# lt3477-buck-boost-flashlight-driver-17mm.net
KiCad netlist of a schematic drawn in EAGLE
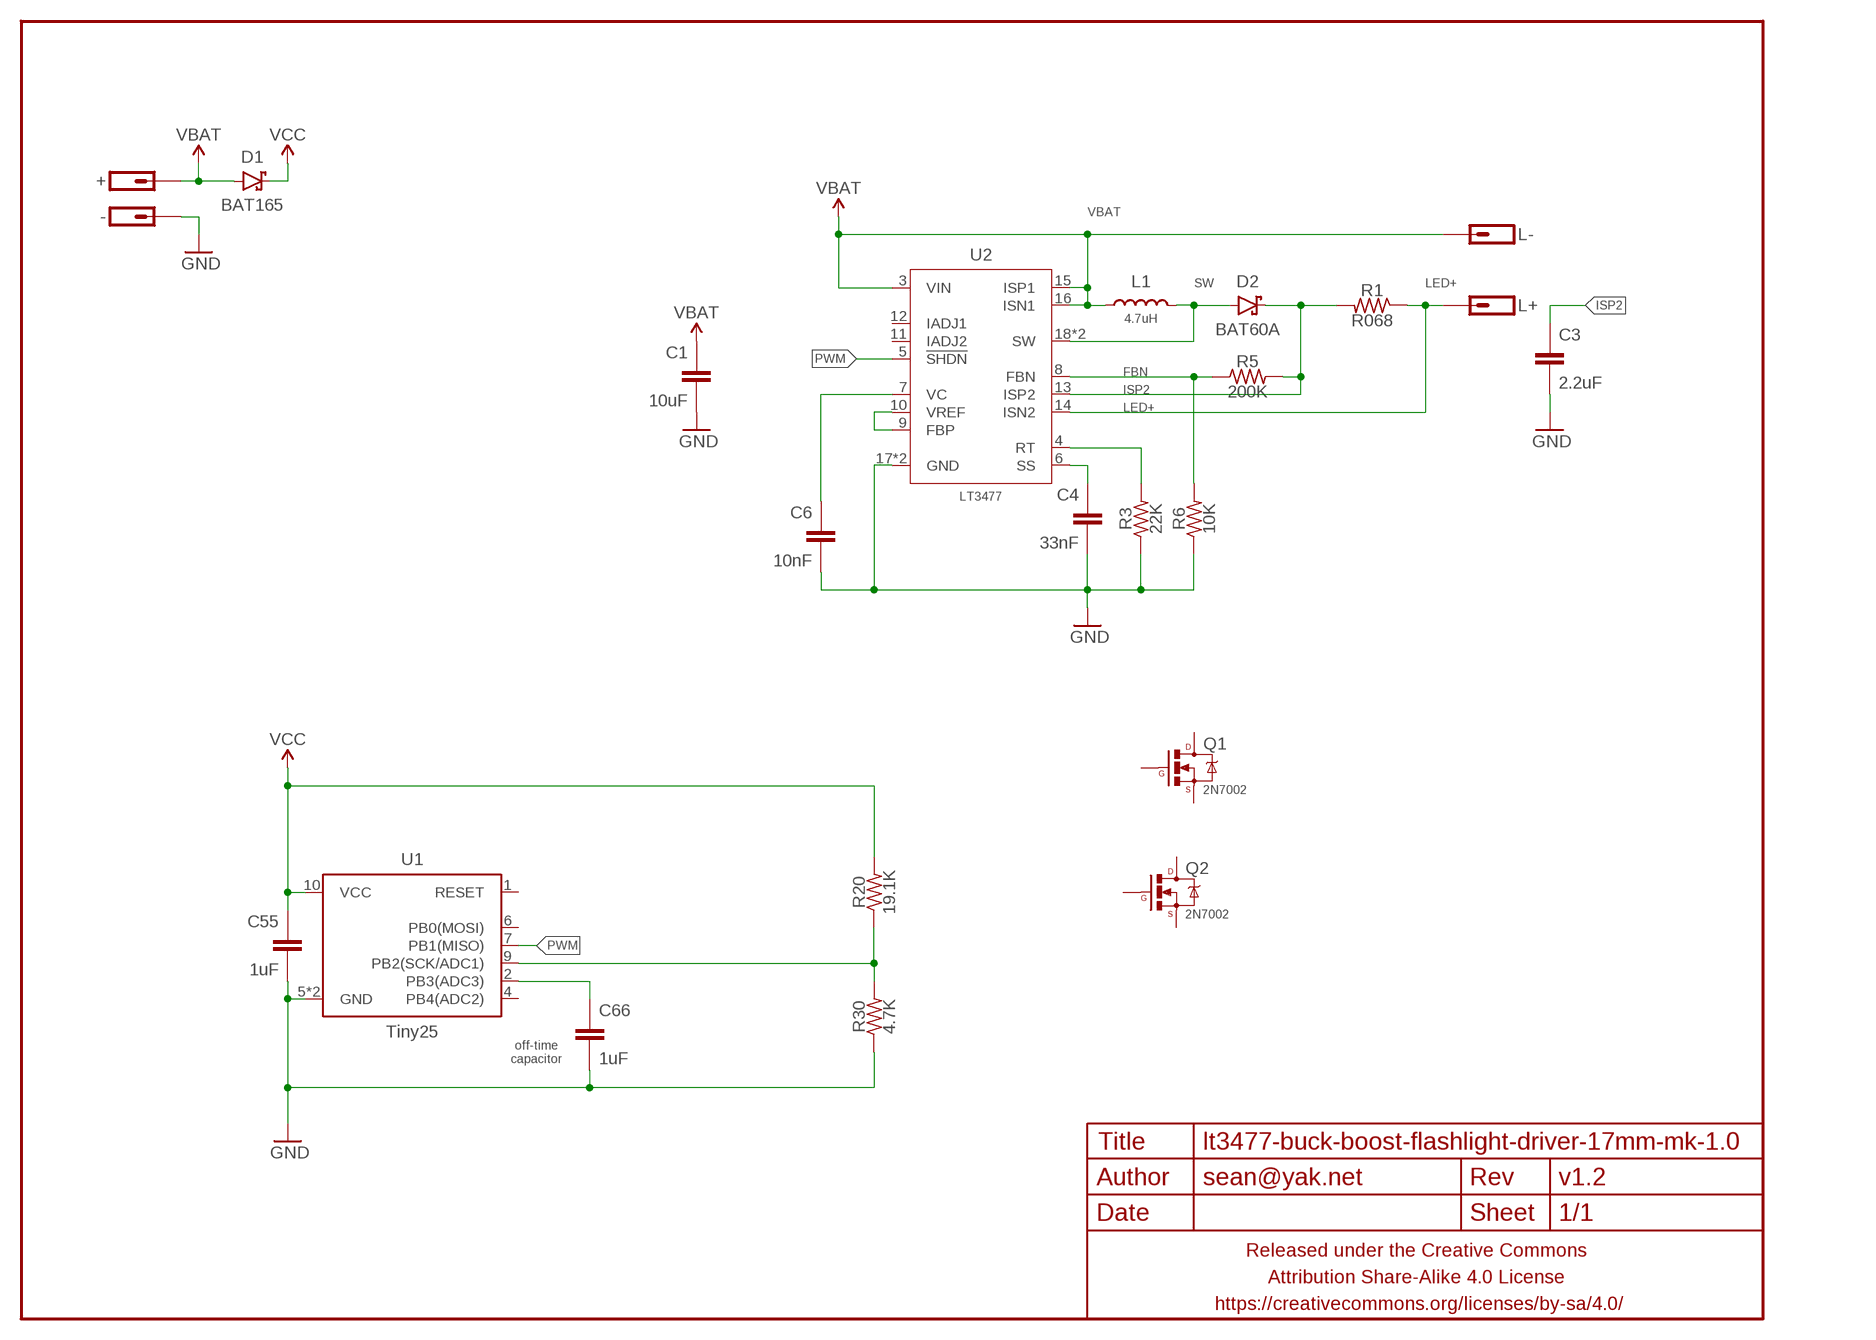
[diagram p0: schematic, sheet 1]

(export (version "E")
  (design (tool "Eeschema 10.0.6"))
  (components
    (comp (ref "+")
      (value "M01PTH-1MM-CIR-NS")
      (footprint "eagle-import:1X01-1MM-CIR-NS")
      (libsource (lib "eagle-import") (part "M01PTH-1MM-CIR-NS"))
    )
    (comp (ref "-")
      (value "M01NOT-A-VIA-NOPE")
      (footprint "eagle-import:1X01_NOSILK_NOSTOP")
      (libsource (lib "eagle-import") (part "M01NOT-A-VIA-NOPE"))
    )
    (comp (ref "C1")
      (value "10uF")
      (footprint "eagle-import:C0603-TIGHTER")
      (libsource (lib "eagle-import") (part "CAPACITOR-CERAMICC0603-TIGHTER"))
    )
    (comp (ref "C3")
      (value "2.2uF")
      (footprint "eagle-import:C0603-TIGHTER")
      (libsource (lib "eagle-import") (part "CAPACITOR-CERAMICC0603-TIGHTER"))
    )
    (comp (ref "C4")
      (value "33nF")
      (footprint "eagle-import:C0402")
      (libsource (lib "eagle-import") (part "CAPACITOR-CERAMICC0402"))
    )
    (comp (ref "C6")
      (value "10nF")
      (footprint "eagle-import:C0402")
      (libsource (lib "eagle-import") (part "CAPACITOR-CERAMICC0402"))
    )
    (comp (ref "C55")
      (value "1uF")
      (footprint "eagle-import:C0603-TIGHTER")
      (libsource (lib "eagle-import") (part "CAPACITOR-CERAMICC0603-TIGHTER"))
    )
    (comp (ref "C66")
      (value "1uF")
      (footprint "eagle-import:C0402")
      (libsource (lib "eagle-import") (part "CAPACITOR-CERAMICC0402"))
    )
    (comp (ref "D1")
      (value "BAT165")
      (footprint "eagle-import:SOD323-SCHOTTKY")
      (libsource (lib "eagle-import") (part "DIODE-SCHOTTKYSOD323"))
    )
    (comp (ref "D2")
      (value "BAT60A")
      (footprint "eagle-import:SOD323-SCHOTTKY")
      (libsource (lib "eagle-import") (part "DIODE-SCHOTTKYSOD323"))
    )
    (comp (ref "FRAME1")
      (value "FRAME-LETTERNO_PACKAGE")
      (footprint "eagle-import:DUMMY")
      (fields
        (field (name "DESIGNER") "sean@yak.net")
        (field (name "VERSION") "v1.2")
        (field (name "DESIGNER_1") "sean@yak.net")
        (field (name "VERSION_1") "v1.2")
      )
      (libsource (lib "eagle-import") (part "FRAME-LETTERNO_PACKAGE"))
    )
    (comp (ref "L+")
      (value "M01PTH-1MM-CIR-NS")
      (footprint "eagle-import:1X01-1MM-CIR-NS")
      (libsource (lib "eagle-import") (part "M01PTH-1MM-CIR-NS"))
    )
    (comp (ref "L-")
      (value "M01PTH-1MM-CIR-NS")
      (footprint "eagle-import:1X01-1MM-CIR-NS")
      (libsource (lib "eagle-import") (part "M01PTH-1MM-CIR-NS"))
    )
    (comp (ref "L1")
      (value "4.7uH")
      (footprint "eagle-import:XAL40X0")
      (libsource (lib "eagle-import") (part "INDUCTORXAL40X0"))
    )
    (comp (ref "Q1")
      (value "2N7002")
      (footprint "eagle-import:SOT23")
      (libsource (lib "eagle-import") (part "MOSFET-NCHANNELIRLML2502"))
    )
    (comp (ref "Q2")
      (value "2N7002")
      (footprint "eagle-import:SOT23")
      (libsource (lib "eagle-import") (part "MOSFET-NCHANNELIRLML2502"))
    )
    (comp (ref "R1")
      (value "R068")
      (footprint "eagle-import:R0805-TIGHTER")
      (libsource (lib "eagle-import") (part "RESISTORR0805-TIGHTER"))
    )
    (comp (ref "R3")
      (value "22K")
      (footprint "eagle-import:R0402")
      (libsource (lib "eagle-import") (part "RESISTORR0402"))
    )
    (comp (ref "R5")
      (value "200K")
      (footprint "eagle-import:R0402")
      (libsource (lib "eagle-import") (part "RESISTORR0402"))
    )
    (comp (ref "R6")
      (value "10K")
      (footprint "eagle-import:R0402")
      (libsource (lib "eagle-import") (part "RESISTORR0402"))
    )
    (comp (ref "R20")
      (value "19.1K")
      (footprint "eagle-import:R0603-TIGHTER")
      (libsource (lib "eagle-import") (part "RESISTORR0603-TIGHTER"))
    )
    (comp (ref "R30")
      (value "4.7K")
      (footprint "eagle-import:R0603-TIGHTER")
      (libsource (lib "eagle-import") (part "RESISTORR0603-TIGHTER"))
    )
    (comp (ref "U1")
      (value "Tiny25")
      (footprint "eagle-import:QFN10(2X5)")
      (libsource (lib "eagle-import") (part "ATTINY1310M1"))
    )
    (comp (ref "U2")
      (value "LT3477")
      (footprint "eagle-import:QFN20-LTC")
      (libsource (lib "eagle-import") (part "LT3477"))
    )
  )
  (nets
    (net (code "1") (name "/FBN") (class "Default")
      (node (ref "R5") (pin "1") (pinfunction "1_1") (pintype "passive"))
      (node (ref "R6") (pin "2") (pinfunction "2_2") (pintype "passive"))
      (node (ref "U2") (pin "8") (pinfunction "FBN_8") (pintype "bidirectional"))
    )
    (net (code "2") (name "/LED+") (class "Default")
      (node (ref "L+") (pin "1") (pinfunction "1_1") (pintype "passive"))
      (node (ref "R1") (pin "1") (pinfunction "1_1") (pintype "passive"))
      (node (ref "U2") (pin "14") (pinfunction "ISN2_14") (pintype "bidirectional"))
    )
    (net (code "3") (name "/SW") (class "Default")
      (node (ref "D2") (pin "A") (pinfunction "A_A") (pintype "passive"))
      (node (ref "L1") (pin "P$2") (pinfunction "2_P$2") (pintype "passive"))
      (node (ref "U2") (pin "18") (pinfunction "SW_18") (pintype "bidirectional"))
      (node (ref "U2") (pin "19") (pinfunction "SW_19") (pintype "bidirectional"))
    )
    (net (code "4") (name "GND") (class "Default")
      (node (ref "-") (pin "P$1") (pinfunction "1_P$1") (pintype "passive"))
      (node (ref "C1") (pin "2") (pinfunction "2_2") (pintype "passive"))
      (node (ref "C3") (pin "2") (pinfunction "2_2") (pintype "passive"))
      (node (ref "C4") (pin "2") (pinfunction "2_2") (pintype "passive"))
      (node (ref "C55") (pin "2") (pinfunction "2_2") (pintype "passive"))
      (node (ref "C6") (pin "2") (pinfunction "2_2") (pintype "passive"))
      (node (ref "C66") (pin "2") (pinfunction "2_2") (pintype "passive"))
      (node (ref "R3") (pin "1") (pinfunction "1_1") (pintype "passive"))
      (node (ref "R30") (pin "1") (pinfunction "1_1") (pintype "passive"))
      (node (ref "R6") (pin "1") (pinfunction "1_1") (pintype "passive"))
      (node (ref "U1") (pin "5") (pinfunction "GND_5") (pintype "bidirectional"))
      (node (ref "U1") (pin "PAD") (pinfunction "GND_PAD") (pintype "bidirectional"))
      (node (ref "U2") (pin "17") (pinfunction "GND_17") (pintype "bidirectional"))
      (node (ref "U2") (pin "PAD") (pinfunction "GND_PAD") (pintype "bidirectional"))
    )
    (net (code "5") (name "ISP2") (class "Default")
      (node (ref "C3") (pin "1") (pinfunction "1_1") (pintype "passive"))
      (node (ref "D2") (pin "C") (pinfunction "C_C") (pintype "passive"))
      (node (ref "R1") (pin "2") (pinfunction "2_2") (pintype "passive"))
      (node (ref "R5") (pin "2") (pinfunction "2_2") (pintype "passive"))
      (node (ref "U2") (pin "13") (pinfunction "ISP2_13") (pintype "bidirectional"))
    )
    (net (code "6") (name "Net-(U1-PB2(SCK{slash}ADC1))") (class "Default")
      (node (ref "R20") (pin "1") (pinfunction "1_1") (pintype "passive"))
      (node (ref "R30") (pin "2") (pinfunction "2_2") (pintype "passive"))
      (node (ref "U1") (pin "9") (pinfunction "PB2(SCK/ADC1)_9") (pintype "bidirectional"))
    )
    (net (code "7") (name "Net-(U1-PB3(ADC3))") (class "Default")
      (node (ref "C66") (pin "1") (pinfunction "1_1") (pintype "passive"))
      (node (ref "U1") (pin "2") (pinfunction "PB3(ADC3)_2") (pintype "bidirectional"))
    )
    (net (code "8") (name "Net-(U2-FBP)") (class "Default")
      (node (ref "U2") (pin "10") (pinfunction "VREF_10") (pintype "bidirectional"))
      (node (ref "U2") (pin "9") (pinfunction "FBP_9") (pintype "bidirectional"))
    )
    (net (code "9") (name "Net-(U2-RT)") (class "Default")
      (node (ref "R3") (pin "2") (pinfunction "2_2") (pintype "passive"))
      (node (ref "U2") (pin "4") (pinfunction "RT_4") (pintype "bidirectional"))
    )
    (net (code "10") (name "Net-(U2-SS)") (class "Default")
      (node (ref "C4") (pin "1") (pinfunction "1_1") (pintype "passive"))
      (node (ref "U2") (pin "6") (pinfunction "SS_6") (pintype "bidirectional"))
    )
    (net (code "11") (name "Net-(U2-VC)") (class "Default")
      (node (ref "C6") (pin "1") (pinfunction "1_1") (pintype "passive"))
      (node (ref "U2") (pin "7") (pinfunction "VC_7") (pintype "bidirectional"))
    )
    (net (code "12") (name "PWM") (class "Default")
      (node (ref "U1") (pin "7") (pinfunction "PB1(MISO)_7") (pintype "bidirectional"))
      (node (ref "U2") (pin "5") (pinfunction "~{SHDN}_5") (pintype "bidirectional"))
    )
    (net (code "13") (name "VBAT") (class "Default")
      (node (ref "+") (pin "1") (pinfunction "1_1") (pintype "passive"))
      (node (ref "C1") (pin "1") (pinfunction "1_1") (pintype "passive"))
      (node (ref "D1") (pin "A") (pinfunction "A_A") (pintype "passive"))
      (node (ref "L-") (pin "1") (pinfunction "1_1") (pintype "passive"))
      (node (ref "L1") (pin "P$1") (pinfunction "1_P$1") (pintype "passive"))
      (node (ref "U2") (pin "15") (pinfunction "ISP1_15") (pintype "bidirectional"))
      (node (ref "U2") (pin "16") (pinfunction "ISN1_16") (pintype "bidirectional"))
      (node (ref "U2") (pin "3") (pinfunction "VIN_3") (pintype "bidirectional"))
    )
    (net (code "14") (name "VCC") (class "Default")
      (node (ref "C55") (pin "1") (pinfunction "1_1") (pintype "passive"))
      (node (ref "D1") (pin "C") (pinfunction "C_C") (pintype "passive"))
      (node (ref "R20") (pin "2") (pinfunction "2_2") (pintype "passive"))
      (node (ref "U1") (pin "10") (pinfunction "VCC_10") (pintype "bidirectional"))
    )
    (net (code "15") (name "unconnected-(Q1-D-Pad3)") (class "Default")
      (node (ref "Q1") (pin "3") (pinfunction "D_3") (pintype "passive"))
    )
    (net (code "16") (name "unconnected-(Q1-G-Pad1)") (class "Default")
      (node (ref "Q1") (pin "1") (pinfunction "G_1") (pintype "passive"))
    )
    (net (code "17") (name "unconnected-(Q1-S-Pad2)") (class "Default")
      (node (ref "Q1") (pin "2") (pinfunction "S_2") (pintype "passive"))
    )
    (net (code "18") (name "unconnected-(Q2-D-Pad3)") (class "Default")
      (node (ref "Q2") (pin "3") (pinfunction "D_3") (pintype "passive"))
    )
    (net (code "19") (name "unconnected-(Q2-G-Pad1)") (class "Default")
      (node (ref "Q2") (pin "1") (pinfunction "G_1") (pintype "passive"))
    )
    (net (code "20") (name "unconnected-(Q2-S-Pad2)") (class "Default")
      (node (ref "Q2") (pin "2") (pinfunction "S_2") (pintype "passive"))
    )
    (net (code "21") (name "unconnected-(U1-PB0(MOSI)-Pad6)") (class "Default")
      (node (ref "U1") (pin "6") (pinfunction "PB0(MOSI)_6") (pintype "bidirectional"))
    )
    (net (code "22") (name "unconnected-(U1-PB4(ADC2)-Pad4)") (class "Default")
      (node (ref "U1") (pin "4") (pinfunction "PB4(ADC2)_4") (pintype "bidirectional"))
    )
    (net (code "23") (name "unconnected-(U1-RESET-Pad1)") (class "Default")
      (node (ref "U1") (pin "1") (pinfunction "RESET_1") (pintype "bidirectional"))
    )
    (net (code "24") (name "unconnected-(U2-IADJ1-Pad12)") (class "Default")
      (node (ref "U2") (pin "12") (pinfunction "IADJ1_12") (pintype "bidirectional"))
    )
    (net (code "25") (name "unconnected-(U2-IADJ2-Pad11)") (class "Default")
      (node (ref "U2") (pin "11") (pinfunction "IADJ2_11") (pintype "bidirectional"))
    )
  )
)
